# Adafruit_Feather_RP2040_Prop-Maker.net
KiCad netlist of a schematic drawn in EAGLE
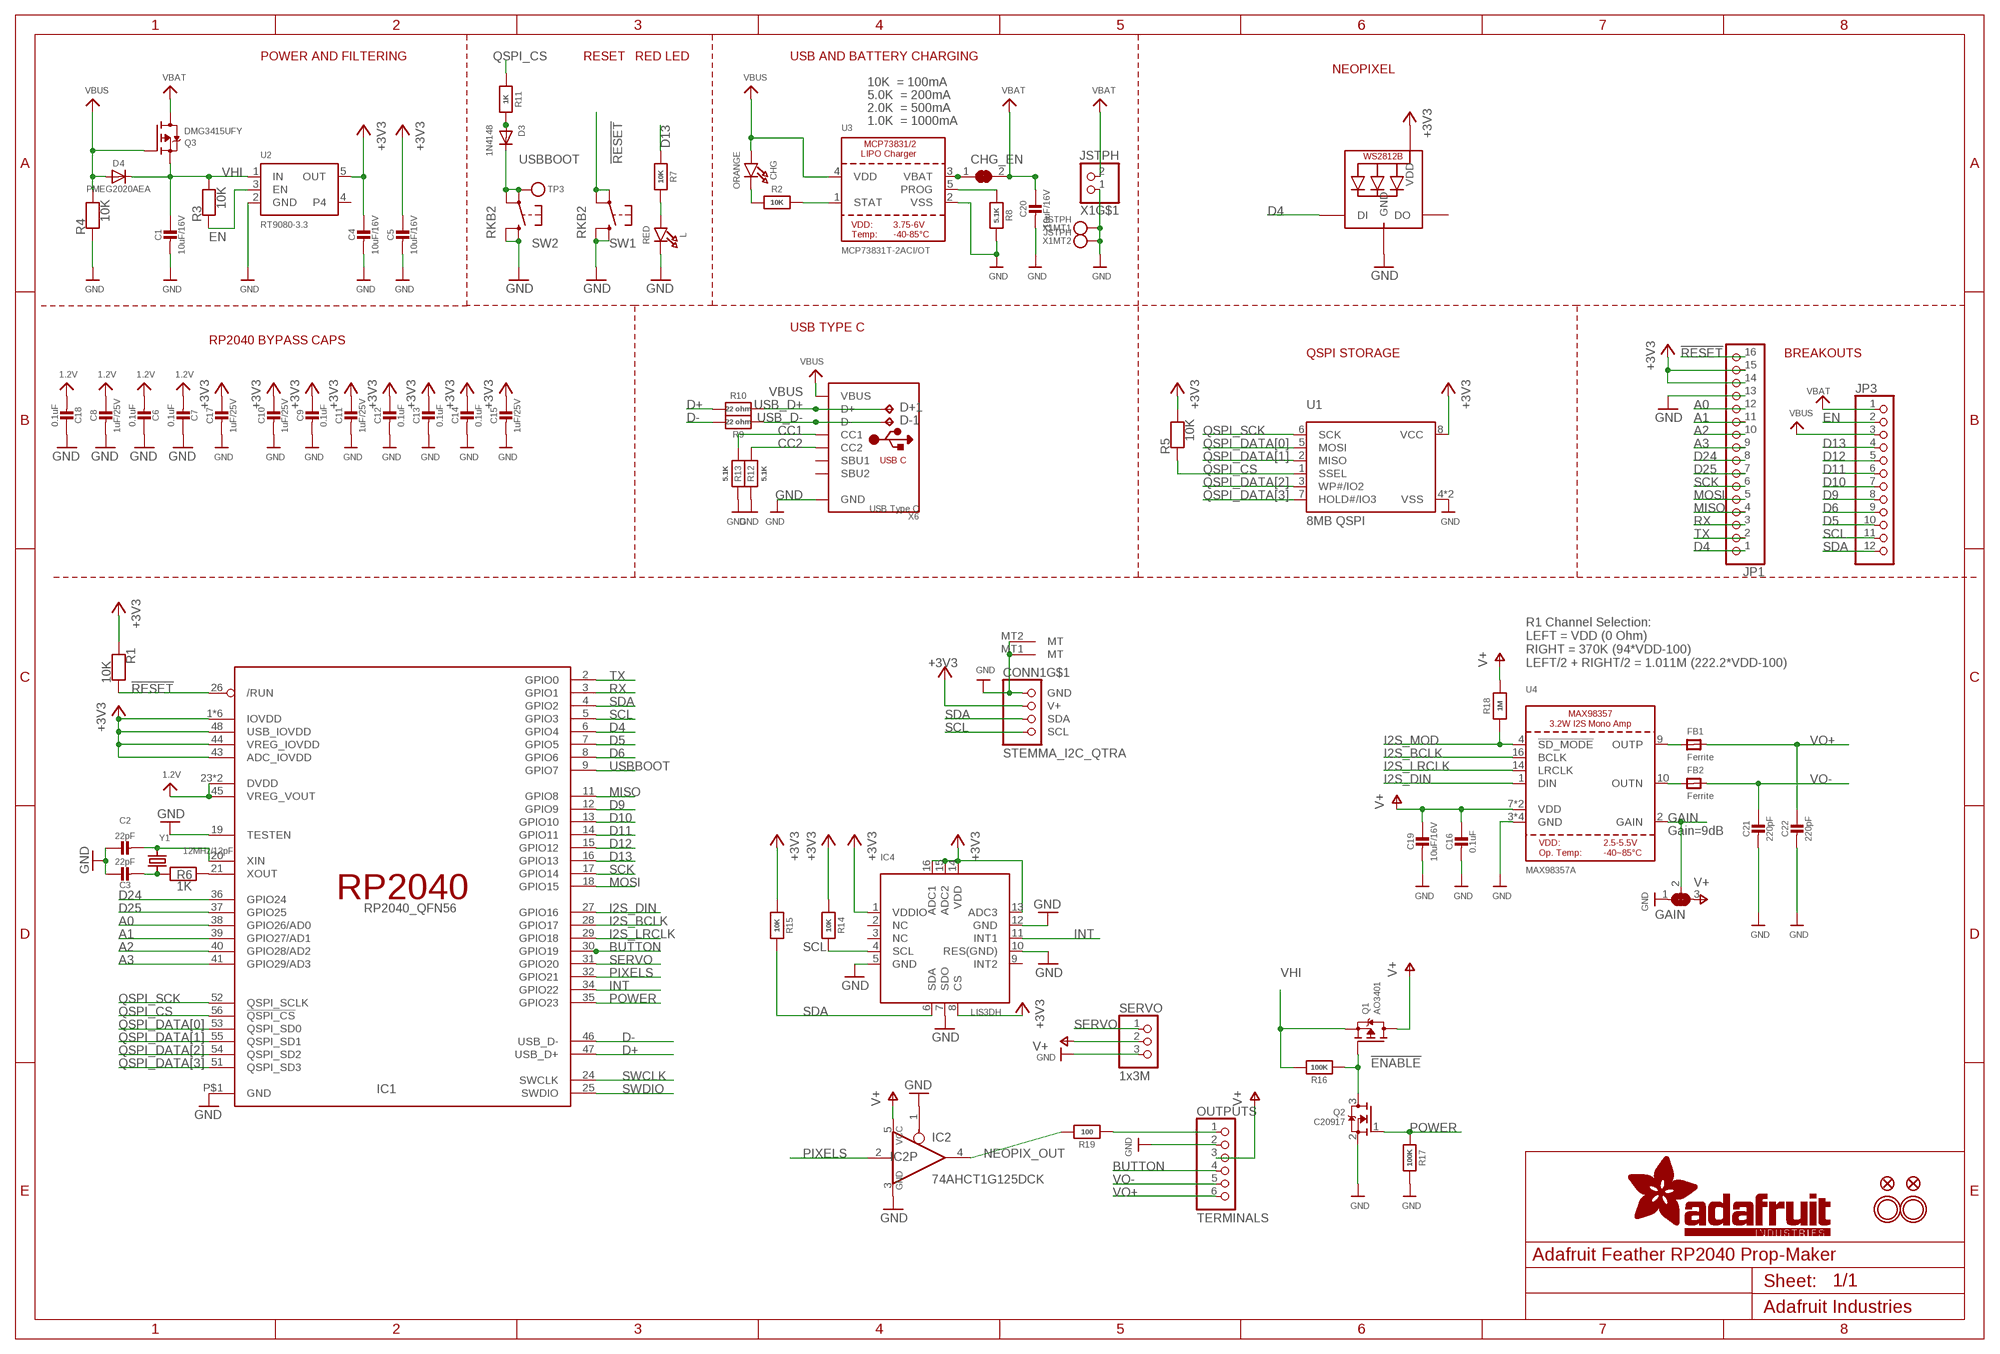
[diagram p0: schematic, sheet 1]

(export (version "E")
  (design (tool "Eeschema 10.0.6"))
  (components
    (comp (ref "C1")
      (value "10uF/16V")
      (footprint "eagle-import:0805-NO")
      (libsource (lib "eagle-import") (part "CAP_CERAMIC0805-NOOUTLINE"))
    )
    (comp (ref "C2")
      (value "22pF")
      (footprint "eagle-import:_0402NO")
      (libsource (lib "eagle-import") (part "CAP_CERAMIC_0402NO"))
    )
    (comp (ref "C3")
      (value "22pF")
      (footprint "eagle-import:_0402NO")
      (libsource (lib "eagle-import") (part "CAP_CERAMIC_0402NO"))
    )
    (comp (ref "C4")
      (value "10uF/16V")
      (footprint "eagle-import:0805-NO")
      (fields (field (name "REV") "B"))
      (libsource (lib "eagle-import") (part "CAP_CERAMIC0805-NOOUTLINE"))
    )
    (comp (ref "C5")
      (value "10uF/16V")
      (footprint "eagle-import:0805-NO")
      (libsource (lib "eagle-import") (part "CAP_CERAMIC0805-NOOUTLINE"))
    )
    (comp (ref "C6")
      (value "0.1uF")
      (footprint "eagle-import:_0402NO")
      (libsource (lib "eagle-import") (part "CAP_CERAMIC_0402NO"))
    )
    (comp (ref "C7")
      (value "0.1uF")
      (footprint "eagle-import:_0402NO")
      (libsource (lib "eagle-import") (part "CAP_CERAMIC_0402NO"))
    )
    (comp (ref "C8")
      (value "1uF/25V")
      (footprint "eagle-import:_0402NO")
      (libsource (lib "eagle-import") (part "CAP_CERAMIC_0402NO"))
    )
    (comp (ref "C9")
      (value "0.1uF")
      (footprint "eagle-import:_0402NO")
      (libsource (lib "eagle-import") (part "CAP_CERAMIC_0402NO"))
    )
    (comp (ref "C10")
      (value "1uF/25V")
      (footprint "eagle-import:_0402NO")
      (libsource (lib "eagle-import") (part "CAP_CERAMIC_0402NO"))
    )
    (comp (ref "C11")
      (value "1uF/25V")
      (footprint "eagle-import:_0402NO")
      (libsource (lib "eagle-import") (part "CAP_CERAMIC_0402NO"))
    )
    (comp (ref "C12")
      (value "0.1uF")
      (footprint "eagle-import:_0402NO")
      (libsource (lib "eagle-import") (part "CAP_CERAMIC_0402NO"))
    )
    (comp (ref "C13")
      (value "0.1uF")
      (footprint "eagle-import:_0402NO")
      (libsource (lib "eagle-import") (part "CAP_CERAMIC_0402NO"))
    )
    (comp (ref "C14")
      (value "0.1uF")
      (footprint "eagle-import:_0402NO")
      (libsource (lib "eagle-import") (part "CAP_CERAMIC_0402NO"))
    )
    (comp (ref "C15")
      (value "1uF/25V")
      (footprint "eagle-import:_0402NO")
      (libsource (lib "eagle-import") (part "CAP_CERAMIC_0402NO"))
    )
    (comp (ref "C16")
      (value "0.1uF")
      (footprint "eagle-import:_0402NO")
      (libsource (lib "eagle-import") (part "CAP_CERAMIC_0402NO"))
    )
    (comp (ref "C17")
      (value "1uF/25V")
      (footprint "eagle-import:_0402NO")
      (libsource (lib "eagle-import") (part "CAP_CERAMIC_0402NO"))
    )
    (comp (ref "C18")
      (value "0.1uF")
      (footprint "eagle-import:_0402NO")
      (libsource (lib "eagle-import") (part "CAP_CERAMIC_0402NO"))
    )
    (comp (ref "C19")
      (value "10uF/16V")
      (footprint "eagle-import:0805-NO")
      (libsource (lib "eagle-import") (part "CAP_CERAMIC0805-NOOUTLINE"))
    )
    (comp (ref "C20")
      (value "10uF/16V")
      (footprint "eagle-import:0805-NO")
      (libsource (lib "eagle-import") (part "CAP_CERAMIC0805-NOOUTLINE"))
    )
    (comp (ref "C21")
      (value "220pF")
      (footprint "eagle-import:_0402NO")
      (libsource (lib "eagle-import") (part "CAP_CERAMIC_0402NO"))
    )
    (comp (ref "C22")
      (value "220pF")
      (footprint "eagle-import:_0402NO")
      (libsource (lib "eagle-import") (part "CAP_CERAMIC_0402NO"))
    )
    (comp (ref "CHG")
      (value "ORANGE")
      (footprint "eagle-import:CHIPLED_0603_NOOUTLINE")
      (libsource (lib "eagle-import") (part "LED0603_NOOUTLINE"))
    )
    (comp (ref "CHG_EN")
      (value "SOLDERJUMPER_CLOSED")
      (footprint "eagle-import:SOLDERJUMPER_CLOSEDWIRE")
      (libsource (lib "eagle-import") (part "SOLDERJUMPER_CLOSED"))
    )
    (comp (ref "CONN1")
      (value "STEMMA_I2C_QTRA")
      (footprint "eagle-import:JST_SH4_RA")
      (libsource (lib "eagle-import") (part "STEMMA_I2C_QTRA"))
    )
    (comp (ref "D+1")
      (value "TPB1,27")
      (footprint "eagle-import:B1,27")
      (libsource (lib "eagle-import") (part "TPB1,27"))
    )
    (comp (ref "D-1")
      (value "TPB1,27")
      (footprint "eagle-import:B1,27")
      (libsource (lib "eagle-import") (part "TPB1,27"))
    )
    (comp (ref "D3")
      (value "1N4148")
      (footprint "eagle-import:SOD-323_MINI")
      (libsource (lib "eagle-import") (part "DIODE_SOD323MINI"))
    )
    (comp (ref "D4")
      (value "PMEG2020AEA")
      (footprint "eagle-import:SOD-323F")
      (libsource (lib "eagle-import") (part "DIODESOD-323F"))
    )
    (comp (ref "FB1")
      (value "Ferrite")
      (footprint "eagle-import:0603-NO")
      (libsource (lib "eagle-import") (part "FERRITE-0603NO"))
    )
    (comp (ref "FB2")
      (value "Ferrite")
      (footprint "eagle-import:0603-NO")
      (libsource (lib "eagle-import") (part "FERRITE-0603NO"))
    )
    (comp (ref "GAIN")
      (value "SOLDERJUMPER_2WAY")
      (footprint "eagle-import:SOLDERJUMPER_2WAY_OPEN_NOPASTE")
      (libsource (lib "eagle-import") (part "SOLDERJUMPER_2WAY"))
    )
    (comp (ref "IC1")
      (value "RP2040_QFN56")
      (footprint "eagle-import:QFN56_7MM_REDUCEDEPAD")
      (libsource (lib "eagle-import") (part "RP2040_QFN56"))
    )
    (comp (ref "IC2")
      (value "74AHCT1G125DCK")
      (footprint "eagle-import:SC70-5")
      (libsource (lib "eagle-import") (part "741G125DCKAHCT"))
    )
    (comp (ref "IC4")
      (value "LIS3DH")
      (footprint "eagle-import:LGA16_3X3MM")
      (libsource (lib "eagle-import") (part "ACCEL_LIS3DHTR"))
    )
    (comp (ref "JP1")
      (value "HEADER-1X16ROUND")
      (footprint "eagle-import:1X16_ROUND")
      (libsource (lib "eagle-import") (part "HEADER-1X16ROUND"))
    )
    (comp (ref "JP3")
      (value "HEADER-1X12")
      (footprint "eagle-import:1X12_ROUND")
      (libsource (lib "eagle-import") (part "HEADER-1X12"))
    )
    (comp (ref "L")
      (value "RED")
      (footprint "eagle-import:CHIPLED_0603_NOOUTLINE")
      (libsource (lib "eagle-import") (part "LED0603_NOOUTLINE"))
    )
    (comp (ref "LED1")
      (value "WS2812B_SK6805_1515")
      (footprint "eagle-import:SK6805_1515")
      (libsource (lib "eagle-import") (part "WS2812B_SK6805_1515"))
    )
    (comp (ref "OUTPUTS")
      (value "TERMINALS")
      (footprint "eagle-import:1X06_OVAL")
      (libsource (lib "eagle-import") (part "HEADER-1X6"))
    )
    (comp (ref "Q1")
      (value "AO3401")
      (footprint "eagle-import:SOT23-WIDE")
      (libsource (lib "eagle-import") (part "MOSFET-PWIDE"))
    )
    (comp (ref "Q2")
      (value "C20917")
      (footprint "eagle-import:SOT23-WIDE")
      (libsource (lib "eagle-import") (part "MOSFET-NWIDE"))
    )
    (comp (ref "Q3")
      (value "DMG3415UFY")
      (footprint "eagle-import:DFN2015-3")
      (libsource (lib "eagle-import") (part "MOSFET-P_DFN2015"))
    )
    (comp (ref "R1")
      (value "10K")
      (footprint "eagle-import:_0402NO")
      (libsource (lib "eagle-import") (part "RESISTOR_0402NO"))
    )
    (comp (ref "R2")
      (value "10K")
      (footprint "eagle-import:_0402NO")
      (libsource (lib "eagle-import") (part "RESISTOR_0402NO"))
    )
    (comp (ref "R3")
      (value "10K")
      (footprint "eagle-import:_0402NO")
      (libsource (lib "eagle-import") (part "RESISTOR_0402NO"))
    )
    (comp (ref "R4")
      (value "10K")
      (footprint "eagle-import:_0402NO")
      (libsource (lib "eagle-import") (part "RESISTOR_0402NO"))
    )
    (comp (ref "R5")
      (value "10K")
      (footprint "eagle-import:_0402NO")
      (libsource (lib "eagle-import") (part "RESISTOR_0402NO"))
    )
    (comp (ref "R6")
      (value "1K")
      (footprint "eagle-import:_0402NO")
      (libsource (lib "eagle-import") (part "RESISTOR_0402NO"))
    )
    (comp (ref "R7")
      (value "10K")
      (footprint "eagle-import:_0402NO")
      (libsource (lib "eagle-import") (part "RESISTOR_0402NO"))
    )
    (comp (ref "R8")
      (value "5.1K")
      (footprint "eagle-import:_0402NO")
      (libsource (lib "eagle-import") (part "RESISTOR_0402NO"))
    )
    (comp (ref "R9")
      (value "22 ohm")
      (footprint "eagle-import:_0402NO")
      (libsource (lib "eagle-import") (part "RESISTOR_0402NO"))
    )
    (comp (ref "R10")
      (value "22 ohm")
      (footprint "eagle-import:_0402NO")
      (libsource (lib "eagle-import") (part "RESISTOR_0402NO"))
    )
    (comp (ref "R11")
      (value "1K")
      (footprint "eagle-import:_0402NO")
      (libsource (lib "eagle-import") (part "RESISTOR_0402NO"))
    )
    (comp (ref "R12")
      (value "5.1K")
      (footprint "eagle-import:_0402NO")
      (libsource (lib "eagle-import") (part "RESISTOR_0402NO"))
    )
    (comp (ref "R13")
      (value "5.1K")
      (footprint "eagle-import:_0402NO")
      (libsource (lib "eagle-import") (part "RESISTOR_0402NO"))
    )
    (comp (ref "R14")
      (value "10K")
      (footprint "eagle-import:_0402NO")
      (libsource (lib "eagle-import") (part "RESISTOR_0402NO"))
    )
    (comp (ref "R15")
      (value "10K")
      (footprint "eagle-import:_0402NO")
      (libsource (lib "eagle-import") (part "RESISTOR_0402NO"))
    )
    (comp (ref "R16")
      (value "100K")
      (footprint "eagle-import:_0402NO")
      (libsource (lib "eagle-import") (part "RESISTOR_0402NO"))
    )
    (comp (ref "R17")
      (value "100K")
      (footprint "eagle-import:_0402NO")
      (libsource (lib "eagle-import") (part "RESISTOR_0402NO"))
    )
    (comp (ref "R18")
      (value "1M")
      (footprint "eagle-import:_0402NO")
      (libsource (lib "eagle-import") (part "RESISTOR_0402NO"))
    )
    (comp (ref "R19")
      (value "100")
      (footprint "eagle-import:_0402NO")
      (libsource (lib "eagle-import") (part "RESISTOR_0402NO"))
    )
    (comp (ref "SERVO")
      (value "1x3M")
      (footprint "eagle-import:1X03_ROUND_76")
      (libsource (lib "eagle-import") (part "HEADER-1X376MIL"))
    )
    (comp (ref "SW1")
      (value "RKB2")
      (footprint "eagle-import:BTN_RKB2_4.6X2.8")
      (libsource (lib "eagle-import") (part "SWITCH_TACT_SMT_RKB2"))
    )
    (comp (ref "SW2")
      (value "RKB2")
      (footprint "eagle-import:BTN_RKB2_4.6X2.8")
      (libsource (lib "eagle-import") (part "SWITCH_TACT_SMT_RKB2"))
    )
    (comp (ref "TP3")
      (value "TESTPOINTROUND1.5MMNO")
      (footprint "eagle-import:TESTPOINT_ROUND_1.5MM_NO")
      (libsource (lib "eagle-import") (part "TESTPOINTROUND1.5MMNO"))
    )
    (comp (ref "U$31")
      (value "MOUNTINGHOLE2.5")
      (footprint "eagle-import:MOUNTINGHOLE_2.5_PLATED")
      (libsource (lib "eagle-import") (part "MOUNTINGHOLE2.5"))
    )
    (comp (ref "U$32")
      (value "MOUNTINGHOLE2.5")
      (footprint "eagle-import:MOUNTINGHOLE_2.5_PLATED")
      (libsource (lib "eagle-import") (part "MOUNTINGHOLE2.5"))
    )
    (comp (ref "U$34")
      (value "FIDUCIAL_1MM")
      (footprint "eagle-import:FIDUCIAL_1MM")
      (libsource (lib "eagle-import") (part "FIDUCIAL_1MM"))
    )
    (comp (ref "U$35")
      (value "FIDUCIAL_1MM")
      (footprint "eagle-import:FIDUCIAL_1MM")
      (libsource (lib "eagle-import") (part "FIDUCIAL_1MM"))
    )
    (comp (ref "U1")
      (value "8MB QSPI")
      (footprint "eagle-import:USON8_4X4")
      (libsource (lib "eagle-import") (part "SPIFLASH_8PIN_4X4"))
    )
    (comp (ref "U2")
      (value "RT9080-3.3")
      (footprint "eagle-import:SOT23-5")
      (fields (field (name "JLC_ROTATION") "0"))
      (libsource (lib "eagle-import") (part "VREG_SOT23-5"))
    )
    (comp (ref "U3")
      (value "MCP73831T-2ACI/OT")
      (footprint "eagle-import:SOT23-5")
      (fields (field (name "JLC_ROTATION") "0"))
      (libsource (lib "eagle-import") (part "MCP73831/2"))
    )
    (comp (ref "U4")
      (value "MAX98357A")
      (footprint "eagle-import:QFN16_3MM")
      (libsource (lib "eagle-import") (part "AUDIOAMP_MAX98357"))
    )
    (comp (ref "X1")
      (value "JSTPH")
      (footprint "eagle-import:JSTPH2_BATT")
      (libsource (lib "eagle-import") (part "CON_JST_PH_2PIN_MT_BATT"))
    )
    (comp (ref "X6")
      (value "USB Type C")
      (footprint "eagle-import:USB_C_CUSB31-CFM2AX-01-X")
      (libsource (lib "eagle-import") (part "USB_C"))
    )
    (comp (ref "Y1")
      (value "12MHz/12pF")
      (footprint "eagle-import:CRYSTAL_2.5X2")
      (libsource (lib "eagle-import") (part "CRYSTAL2.5X2.0"))
    )
  )
  (nets
    (net (code "1") (name "+3V3") (class "Default")
      (node (ref "C10") (pin "1") (pinfunction "1_1") (pintype "passive"))
      (node (ref "C11") (pin "1") (pinfunction "1_1") (pintype "passive"))
      (node (ref "C12") (pin "1") (pinfunction "1_1") (pintype "passive"))
      (node (ref "C13") (pin "1") (pinfunction "1_1") (pintype "passive"))
      (node (ref "C14") (pin "1") (pinfunction "1_1") (pintype "passive"))
      (node (ref "C15") (pin "1") (pinfunction "1_1") (pintype "passive"))
      (node (ref "C17") (pin "1") (pinfunction "1_1") (pintype "passive"))
      (node (ref "C4") (pin "1") (pinfunction "1_1") (pintype "passive"))
      (node (ref "C5") (pin "1") (pinfunction "1_1") (pintype "passive"))
      (node (ref "C9") (pin "1") (pinfunction "1_1") (pintype "passive"))
      (node (ref "CONN1") (pin "2") (pinfunction "V+_2") (pintype "passive"))
      (node (ref "IC1") (pin "1") (pinfunction "IOVDD_1") (pintype "power_in"))
      (node (ref "IC1") (pin "10") (pinfunction "IOVDD_10") (pintype "power_in"))
      (node (ref "IC1") (pin "22") (pinfunction "IOVDD_22") (pintype "power_in"))
      (node (ref "IC1") (pin "33") (pinfunction "IOVDD_33") (pintype "power_in"))
      (node (ref "IC1") (pin "42") (pinfunction "IOVDD_42") (pintype "power_in"))
      (node (ref "IC1") (pin "43") (pinfunction "ADC_IOVDD_43") (pintype "power_in"))
      (node (ref "IC1") (pin "44") (pinfunction "VREG_IOVDD_44") (pintype "power_in"))
      (node (ref "IC1") (pin "48") (pinfunction "USB_IOVDD_48") (pintype "power_in"))
      (node (ref "IC1") (pin "49") (pinfunction "IOVDD_49") (pintype "power_in"))
      (node (ref "IC4") (pin "1") (pinfunction "VDDIO_1") (pintype "power_in"))
      (node (ref "IC4") (pin "13") (pinfunction "ADC3_13") (pintype "input"))
      (node (ref "IC4") (pin "14") (pinfunction "VDD_14") (pintype "power_in"))
      (node (ref "IC4") (pin "15") (pinfunction "ADC2_15") (pintype "input"))
      (node (ref "IC4") (pin "16") (pinfunction "ADC1_16") (pintype "input"))
      (node (ref "IC4") (pin "8") (pinfunction "CS_8") (pintype "input"))
      (node (ref "JP1") (pin "14") (pinfunction "14_14") (pintype "passive"))
      (node (ref "JP1") (pin "15") (pinfunction "15_15") (pintype "passive"))
      (node (ref "LED1") (pin "2") (pinfunction "VDD_2") (pintype "power_in"))
      (node (ref "R1") (pin "1") (pinfunction "1_1") (pintype "passive"))
      (node (ref "R14") (pin "1") (pinfunction "1_1") (pintype "passive"))
      (node (ref "R15") (pin "1") (pinfunction "1_1") (pintype "passive"))
      (node (ref "R5") (pin "2") (pinfunction "2_2") (pintype "passive"))
      (node (ref "U1") (pin "8") (pinfunction "VCC_8") (pintype "bidirectional"))
      (node (ref "U2") (pin "5") (pinfunction "OUT_5") (pintype "power_in"))
    )
    (net (code "2") (name "/A0") (class "Default")
      (node (ref "IC1") (pin "38") (pinfunction "GPIO26/AD0_38") (pintype "bidirectional"))
      (node (ref "JP1") (pin "12") (pinfunction "12_12") (pintype "passive"))
    )
    (net (code "3") (name "/A1") (class "Default")
      (node (ref "IC1") (pin "39") (pinfunction "GPIO27/AD1_39") (pintype "bidirectional"))
      (node (ref "JP1") (pin "11") (pinfunction "11_11") (pintype "passive"))
    )
    (net (code "4") (name "/A2") (class "Default")
      (node (ref "IC1") (pin "40") (pinfunction "GPIO28/AD2_40") (pintype "bidirectional"))
      (node (ref "JP1") (pin "10") (pinfunction "10_10") (pintype "passive"))
    )
    (net (code "5") (name "/A3") (class "Default")
      (node (ref "IC1") (pin "41") (pinfunction "GPIO29/AD3_41") (pintype "bidirectional"))
      (node (ref "JP1") (pin "9") (pinfunction "9_9") (pintype "passive"))
    )
    (net (code "6") (name "/BUTTON") (class "Default")
      (node (ref "IC1") (pin "30") (pinfunction "GPIO19_30") (pintype "bidirectional"))
      (node (ref "OUTPUTS") (pin "4") (pinfunction "4_4") (pintype "passive"))
    )
    (net (code "7") (name "/CC1") (class "Default")
      (node (ref "R13") (pin "2") (pinfunction "2_2") (pintype "passive"))
      (node (ref "X6") (pin "A5") (pinfunction "CC1_A5") (pintype "bidirectional"))
    )
    (net (code "8") (name "/CC2") (class "Default")
      (node (ref "R12") (pin "2") (pinfunction "2_2") (pintype "passive"))
      (node (ref "X6") (pin "B5") (pinfunction "CC2_B5") (pintype "bidirectional"))
    )
    (net (code "9") (name "/D+") (class "Default")
      (node (ref "IC1") (pin "47") (pinfunction "USB_D+_47") (pintype "bidirectional"))
      (node (ref "R10") (pin "2") (pinfunction "2_2") (pintype "passive"))
    )
    (net (code "10") (name "/D-") (class "Default")
      (node (ref "IC1") (pin "46") (pinfunction "USB_D-_46") (pintype "bidirectional"))
      (node (ref "R9") (pin "2") (pinfunction "2_2") (pintype "passive"))
    )
    (net (code "11") (name "/D4") (class "Default")
      (node (ref "IC1") (pin "6") (pinfunction "GPIO4_6") (pintype "bidirectional"))
      (node (ref "JP1") (pin "1") (pinfunction "1_1") (pintype "passive"))
      (node (ref "LED1") (pin "1") (pinfunction "DI_1") (pintype "input"))
    )
    (net (code "12") (name "/D5") (class "Default")
      (node (ref "IC1") (pin "7") (pinfunction "GPIO5_7") (pintype "bidirectional"))
      (node (ref "JP3") (pin "10") (pinfunction "10_10") (pintype "passive"))
    )
    (net (code "13") (name "/D6") (class "Default")
      (node (ref "IC1") (pin "8") (pinfunction "GPIO6_8") (pintype "bidirectional"))
      (node (ref "JP3") (pin "9") (pinfunction "9_9") (pintype "passive"))
    )
    (net (code "14") (name "/D9") (class "Default")
      (node (ref "IC1") (pin "12") (pinfunction "GPIO9_12") (pintype "bidirectional"))
      (node (ref "JP3") (pin "8") (pinfunction "8_8") (pintype "passive"))
    )
    (net (code "15") (name "/D10") (class "Default")
      (node (ref "IC1") (pin "13") (pinfunction "GPIO10_13") (pintype "bidirectional"))
      (node (ref "JP3") (pin "7") (pinfunction "7_7") (pintype "passive"))
    )
    (net (code "16") (name "/D11") (class "Default")
      (node (ref "IC1") (pin "14") (pinfunction "GPIO11_14") (pintype "bidirectional"))
      (node (ref "JP3") (pin "6") (pinfunction "6_6") (pintype "passive"))
    )
    (net (code "17") (name "/D12") (class "Default")
      (node (ref "IC1") (pin "15") (pinfunction "GPIO12_15") (pintype "bidirectional"))
      (node (ref "JP3") (pin "5") (pinfunction "5_5") (pintype "passive"))
    )
    (net (code "18") (name "/D13") (class "Default")
      (node (ref "IC1") (pin "16") (pinfunction "GPIO13_16") (pintype "bidirectional"))
      (node (ref "JP3") (pin "4") (pinfunction "4_4") (pintype "passive"))
      (node (ref "R7") (pin "1") (pinfunction "1_1") (pintype "passive"))
    )
    (net (code "19") (name "/D24") (class "Default")
      (node (ref "IC1") (pin "36") (pinfunction "GPIO24_36") (pintype "bidirectional"))
      (node (ref "JP1") (pin "8") (pinfunction "8_8") (pintype "passive"))
    )
    (net (code "20") (name "/D25") (class "Default")
      (node (ref "IC1") (pin "37") (pinfunction "GPIO25_37") (pintype "bidirectional"))
      (node (ref "JP1") (pin "7") (pinfunction "7_7") (pintype "passive"))
    )
    (net (code "21") (name "/EN") (class "Default")
      (node (ref "JP3") (pin "2") (pinfunction "2_2") (pintype "passive"))
      (node (ref "R3") (pin "1") (pinfunction "1_1") (pintype "passive"))
      (node (ref "U2") (pin "3") (pinfunction "EN_3") (pintype "input"))
    )
    (net (code "22") (name "/GAIN") (class "Default")
      (node (ref "GAIN") (pin "2") (pinfunction "2_2") (pintype "passive"))
      (node (ref "U4") (pin "2") (pinfunction "GAIN_2") (pintype "bidirectional"))
    )
    (net (code "23") (name "/I2S_BCLK") (class "Default")
      (node (ref "IC1") (pin "28") (pinfunction "GPIO17_28") (pintype "bidirectional"))
      (node (ref "U4") (pin "16") (pinfunction "BCLK_16") (pintype "bidirectional"))
    )
    (net (code "24") (name "/I2S_DIN") (class "Default")
      (node (ref "IC1") (pin "27") (pinfunction "GPIO16_27") (pintype "bidirectional"))
      (node (ref "U4") (pin "1") (pinfunction "DIN_1") (pintype "bidirectional"))
    )
    (net (code "25") (name "/I2S_LRCLK") (class "Default")
      (node (ref "IC1") (pin "29") (pinfunction "GPIO18_29") (pintype "bidirectional"))
      (node (ref "U4") (pin "14") (pinfunction "LRCLK_14") (pintype "bidirectional"))
    )
    (net (code "26") (name "/I2S_MOD") (class "Default")
      (node (ref "R18") (pin "1") (pinfunction "1_1") (pintype "passive"))
      (node (ref "U4") (pin "4") (pinfunction "~{SD_MODE}_4") (pintype "bidirectional"))
    )
    (net (code "27") (name "/INT") (class "Default")
      (node (ref "IC1") (pin "34") (pinfunction "GPIO22_34") (pintype "bidirectional"))
      (node (ref "IC4") (pin "11") (pinfunction "INT1_11") (pintype "output"))
    )
    (net (code "28") (name "/MISO") (class "Default")
      (node (ref "IC1") (pin "11") (pinfunction "GPIO8_11") (pintype "bidirectional"))
      (node (ref "JP1") (pin "4") (pinfunction "4_4") (pintype "passive"))
    )
    (net (code "29") (name "/MOSI") (class "Default")
      (node (ref "IC1") (pin "18") (pinfunction "GPIO15_18") (pintype "bidirectional"))
      (node (ref "JP1") (pin "5") (pinfunction "5_5") (pintype "passive"))
    )
    (net (code "30") (name "/NEOPIX_OUT") (class "Default")
      (node (ref "IC2") (pin "4") (pinfunction "O_4") (pintype "tri_state"))
      (node (ref "R19") (pin "2") (pinfunction "2_2") (pintype "passive"))
    )
    (net (code "31") (name "/PIXELS") (class "Default")
      (node (ref "IC1") (pin "32") (pinfunction "GPIO21_32") (pintype "bidirectional"))
      (node (ref "IC2") (pin "2") (pinfunction "I_2") (pintype "input"))
    )
    (net (code "32") (name "/POWER") (class "Default")
      (node (ref "IC1") (pin "35") (pinfunction "GPIO23_35") (pintype "bidirectional"))
      (node (ref "Q2") (pin "1") (pinfunction "G_1") (pintype "bidirectional"))
      (node (ref "R17") (pin "1") (pinfunction "1_1") (pintype "passive"))
    )
    (net (code "33") (name "/QSPI_CS") (class "Default")
      (node (ref "IC1") (pin "56") (pinfunction "~{QSPI_CS}_56") (pintype "bidirectional"))
      (node (ref "R11") (pin "1") (pinfunction "1_1") (pintype "passive"))
      (node (ref "R5") (pin "1") (pinfunction "1_1") (pintype "passive"))
      (node (ref "U1") (pin "1") (pinfunction "SSEL_1") (pintype "bidirectional"))
    )
    (net (code "34") (name "/QSPI_DATA[0]") (class "Default")
      (node (ref "IC1") (pin "53") (pinfunction "QSPI_SD0_53") (pintype "bidirectional"))
      (node (ref "U1") (pin "5") (pinfunction "MOSI_5") (pintype "bidirectional"))
    )
    (net (code "35") (name "/QSPI_DATA[1]") (class "Default")
      (node (ref "IC1") (pin "55") (pinfunction "QSPI_SD1_55") (pintype "bidirectional"))
      (node (ref "U1") (pin "2") (pinfunction "MISO_2") (pintype "bidirectional"))
    )
    (net (code "36") (name "/QSPI_DATA[2]") (class "Default")
      (node (ref "IC1") (pin "54") (pinfunction "QSPI_SD2_54") (pintype "bidirectional"))
      (node (ref "U1") (pin "3") (pinfunction "WP#/IO2_3") (pintype "bidirectional"))
    )
    (net (code "37") (name "/QSPI_DATA[3]") (class "Default")
      (node (ref "IC1") (pin "51") (pinfunction "QSPI_SD3_51") (pintype "bidirectional"))
      (node (ref "U1") (pin "7") (pinfunction "HOLD#/IO3_7") (pintype "bidirectional"))
    )
    (net (code "38") (name "/QSPI_SCK") (class "Default")
      (node (ref "IC1") (pin "52") (pinfunction "QSPI_SCLK_52") (pintype "bidirectional"))
      (node (ref "U1") (pin "6") (pinfunction "SCK_6") (pintype "bidirectional"))
    )
    (net (code "39") (name "/RX") (class "Default")
      (node (ref "IC1") (pin "3") (pinfunction "GPIO1_3") (pintype "bidirectional"))
      (node (ref "JP1") (pin "3") (pinfunction "3_3") (pintype "passive"))
    )
    (net (code "40") (name "/SCK") (class "Default")
      (node (ref "IC1") (pin "17") (pinfunction "GPIO14_17") (pintype "bidirectional"))
      (node (ref "JP1") (pin "6") (pinfunction "6_6") (pintype "passive"))
    )
    (net (code "41") (name "/SCL") (class "Default")
      (node (ref "CONN1") (pin "4") (pinfunction "SCL_4") (pintype "passive"))
      (node (ref "IC1") (pin "5") (pinfunction "GPIO3_5") (pintype "bidirectional"))
      (node (ref "IC4") (pin "4") (pinfunction "SCL_4") (pintype "bidirectional"))
      (node (ref "JP3") (pin "11") (pinfunction "11_11") (pintype "passive"))
      (node (ref "R14") (pin "2") (pinfunction "2_2") (pintype "passive"))
    )
    (net (code "42") (name "/SDA") (class "Default")
      (node (ref "CONN1") (pin "3") (pinfunction "SDA_3") (pintype "passive"))
      (node (ref "IC1") (pin "4") (pinfunction "GPIO2_4") (pintype "bidirectional"))
      (node (ref "IC4") (pin "6") (pinfunction "SDA_6") (pintype "bidirectional"))
      (node (ref "JP3") (pin "12") (pinfunction "12_12") (pintype "passive"))
      (node (ref "R15") (pin "2") (pinfunction "2_2") (pintype "passive"))
    )
    (net (code "43") (name "/SERVO") (class "Default")
      (node (ref "IC1") (pin "31") (pinfunction "GPIO20_31") (pintype "bidirectional"))
      (node (ref "SERVO") (pin "1") (pinfunction "1_1") (pintype "passive"))
    )
    (net (code "44") (name "/SWCLK") (class "Default")
      (node (ref "IC1") (pin "24") (pinfunction "SWCLK_24") (pintype "bidirectional"))
    )
    (net (code "45") (name "/SWDIO") (class "Default")
      (node (ref "IC1") (pin "25") (pinfunction "SWDIO_25") (pintype "bidirectional"))
    )
    (net (code "46") (name "/TX") (class "Default")
      (node (ref "IC1") (pin "2") (pinfunction "GPIO0_2") (pintype "bidirectional"))
      (node (ref "JP1") (pin "2") (pinfunction "2_2") (pintype "passive"))
    )
    (net (code "47") (name "/USBBOOT") (class "Default")
      (node (ref "D3") (pin "C") (pinfunction "C_C") (pintype "passive"))
      (node (ref "IC1") (pin "9") (pinfunction "GPIO7_9") (pintype "bidirectional"))
      (node (ref "SW2") (pin "A") (pinfunction "P_A") (pintype "passive"))
      (node (ref "SW2") (pin "A'") (pinfunction "P1_A'") (pintype "passive"))
      (node (ref "TP3") (pin "P$1") (pinfunction "P$1_P$1") (pintype "bidirectional"))
    )
    (net (code "48") (name "/USB_D+") (class "Default")
      (node (ref "D+1") (pin "TP") (pinfunction "TP_TP") (pintype "input"))
      (node (ref "R10") (pin "1") (pinfunction "1_1") (pintype "passive"))
      (node (ref "X6") (pin "A6") (pinfunction "D+_A6") (pintype "bidirectional"))
      (node (ref "X6") (pin "B6") (pinfunction "D+_B6") (pintype "bidirectional"))
    )
    (net (code "49") (name "/USB_D-") (class "Default")
      (node (ref "D-1") (pin "TP") (pinfunction "TP_TP") (pintype "input"))
      (node (ref "R9") (pin "1") (pinfunction "1_1") (pintype "passive"))
      (node (ref "X6") (pin "A7") (pinfunction "D-_A7") (pintype "bidirectional"))
      (node (ref "X6") (pin "B7") (pinfunction "D-_B7") (pintype "bidirectional"))
    )
    (net (code "50") (name "/VHI") (class "Default")
      (node (ref "C1") (pin "1") (pinfunction "1_1") (pintype "passive"))
      (node (ref "D4") (pin "C") (pinfunction "C_C") (pintype "passive"))
      (node (ref "Q1") (pin "2") (pinfunction "S_2") (pintype "passive"))
      (node (ref "Q3") (pin "2") (pinfunction "S_2") (pintype "passive"))
      (node (ref "R16") (pin "2") (pinfunction "2_2") (pintype "passive"))
      (node (ref "R3") (pin "2") (pinfunction "2_2") (pintype "passive"))
      (node (ref "U2") (pin "1") (pinfunction "IN_1") (pintype "power_in"))
    )
    (net (code "51") (name "/VO+") (class "Default")
      (node (ref "C22") (pin "1") (pinfunction "1_1") (pintype "passive"))
      (node (ref "FB1") (pin "2") (pinfunction "P$2_2") (pintype "passive"))
      (node (ref "OUTPUTS") (pin "6") (pinfunction "6_6") (pintype "passive"))
    )
    (net (code "52") (name "/VO-") (class "Default")
      (node (ref "C21") (pin "1") (pinfunction "1_1") (pintype "passive"))
      (node (ref "FB2") (pin "2") (pinfunction "P$2_2") (pintype "passive"))
      (node (ref "OUTPUTS") (pin "5") (pinfunction "5_5") (pintype "passive"))
    )
    (net (code "53") (name "/~{ENABLE}") (class "Default")
      (node (ref "Q1") (pin "1") (pinfunction "G_1") (pintype "passive"))
      (node (ref "Q2") (pin "3") (pinfunction "D_3") (pintype "bidirectional"))
      (node (ref "R16") (pin "1") (pinfunction "1_1") (pintype "passive"))
    )
    (net (code "54") (name "/~{RESET}") (class "Default")
      (node (ref "IC1") (pin "26") (pinfunction "/RUN_26") (pintype "bidirectional"))
      (node (ref "JP1") (pin "16") (pinfunction "16_16") (pintype "passive"))
      (node (ref "R1") (pin "2") (pinfunction "2_2") (pintype "passive"))
      (node (ref "SW1") (pin "A") (pinfunction "P_A") (pintype "passive"))
      (node (ref "SW1") (pin "A'") (pinfunction "P1_A'") (pintype "passive"))
    )
    (net (code "55") (name "1.2V") (class "Default")
      (node (ref "C18") (pin "2") (pinfunction "2_2") (pintype "passive"))
      (node (ref "C6") (pin "2") (pinfunction "2_2") (pintype "passive"))
      (node (ref "C7") (pin "2") (pinfunction "2_2") (pintype "passive"))
      (node (ref "C8") (pin "1") (pinfunction "1_1") (pintype "passive"))
      (node (ref "IC1") (pin "23") (pinfunction "DVDD_23") (pintype "power_in"))
      (node (ref "IC1") (pin "45") (pinfunction "VREG_VOUT_45") (pintype "power_in"))
      (node (ref "IC1") (pin "50") (pinfunction "DVDD_50") (pintype "power_in"))
    )
    (net (code "56") (name "GND") (class "Default")
      (node (ref "C1") (pin "2") (pinfunction "2_2") (pintype "passive"))
      (node (ref "C10") (pin "2") (pinfunction "2_2") (pintype "passive"))
      (node (ref "C11") (pin "2") (pinfunction "2_2") (pintype "passive"))
      (node (ref "C12") (pin "2") (pinfunction "2_2") (pintype "passive"))
      (node (ref "C13") (pin "2") (pinfunction "2_2") (pintype "passive"))
      (node (ref "C14") (pin "2") (pinfunction "2_2") (pintype "passive"))
      (node (ref "C15") (pin "2") (pinfunction "2_2") (pintype "passive"))
      (node (ref "C16") (pin "2") (pinfunction "2_2") (pintype "passive"))
      (node (ref "C17") (pin "2") (pinfunction "2_2") (pintype "passive"))
      (node (ref "C18") (pin "1") (pinfunction "1_1") (pintype "passive"))
      (node (ref "C19") (pin "2") (pinfunction "2_2") (pintype "passive"))
      (node (ref "C2") (pin "1") (pinfunction "1_1") (pintype "passive"))
      (node (ref "C20") (pin "2") (pinfunction "2_2") (pintype "passive"))
      (node (ref "C21") (pin "2") (pinfunction "2_2") (pintype "passive"))
      (node (ref "C22") (pin "2") (pinfunction "2_2") (pintype "passive"))
      (node (ref "C3") (pin "1") (pinfunction "1_1") (pintype "passive"))
      (node (ref "C4") (pin "2") (pinfunction "2_2") (pintype "passive"))
      (node (ref "C5") (pin "2") (pinfunction "2_2") (pintype "passive"))
      (node (ref "C6") (pin "1") (pinfunction "1_1") (pintype "passive"))
      (node (ref "C7") (pin "1") (pinfunction "1_1") (pintype "passive"))
      (node (ref "C8") (pin "2") (pinfunction "2_2") (pintype "passive"))
      (node (ref "C9") (pin "2") (pinfunction "2_2") (pintype "passive"))
      (node (ref "CONN1") (pin "1") (pinfunction "GND_1") (pintype "passive"))
      (node (ref "CONN1") (pin "MT1") (pinfunction "MT_MT1") (pintype "bidirectional"))
      (node (ref "CONN1") (pin "MT2") (pinfunction "MT_MT2") (pintype "bidirectional"))
      (node (ref "GAIN") (pin "1") (pinfunction "1_1") (pintype "passive"))
      (node (ref "IC1") (pin "19") (pinfunction "TESTEN_19") (pintype "input"))
      (node (ref "IC1") (pin "P$1") (pinfunction "GND_P$1") (pintype "power_in"))
      (node (ref "IC2") (pin "1") (pinfunction "OE_1") (pintype "input"))
      (node (ref "IC2") (pin "3") (pinfunction "GND_3") (pintype "power_in"))
      (node (ref "IC4") (pin "10") (pinfunction "RES(GND)_10") (pintype "bidirectional"))
      (node (ref "IC4") (pin "12") (pinfunction "GND_12") (pintype "power_in"))
      (node (ref "IC4") (pin "5") (pinfunction "GND_5") (pintype "power_in"))
      (node (ref "IC4") (pin "7") (pinfunction "SDO_7") (pintype "bidirectional"))
      (node (ref "JP1") (pin "13") (pinfunction "13_13") (pintype "passive"))
      (node (ref "L") (pin "C") (pinfunction "C_C") (pintype "passive"))
      (node (ref "LED1") (pin "4") (pinfunction "GND_4") (pintype "power_in"))
      (node (ref "OUTPUTS") (pin "2") (pinfunction "2_2") (pintype "passive"))
      (node (ref "Q2") (pin "2") (pinfunction "S_2") (pintype "bidirectional"))
      (node (ref "R12") (pin "1") (pinfunction "1_1") (pintype "passive"))
      (node (ref "R13") (pin "1") (pinfunction "1_1") (pintype "passive"))
      (node (ref "R17") (pin "2") (pinfunction "2_2") (pintype "passive"))
      (node (ref "R4") (pin "1") (pinfunction "1_1") (pintype "passive"))
      (node (ref "R8") (pin "2") (pinfunction "2_2") (pintype "passive"))
      (node (ref "SERVO") (pin "3") (pinfunction "3_3") (pintype "passive"))
      (node (ref "SW1") (pin "B") (pinfunction "S_B") (pintype "passive"))
      (node (ref "SW1") (pin "B'") (pinfunction "S1_B'") (pintype "passive"))
      (node (ref "SW2") (pin "B") (pinfunction "S_B") (pintype "passive"))
      (node (ref "SW2") (pin "B'") (pinfunction "S1_B'") (pintype "passive"))
      (node (ref "U1") (pin "4") (pinfunction "VSS_4") (pintype "bidirectional"))
      (node (ref "U1") (pin "PAD") (pinfunction "VSS_PAD") (pintype "bidirectional"))
      (node (ref "U2") (pin "2") (pinfunction "GND_2") (pintype "power_in"))
      (node (ref "U3") (pin "2") (pinfunction "VSS_2") (pintype "power_in"))
      (node (ref "U4") (pin "11") (pinfunction "GND_11") (pintype "power_in"))
      (node (ref "U4") (pin "15") (pinfunction "GND_15") (pintype "power_in"))
      (node (ref "U4") (pin "3") (pinfunction "GND_3") (pintype "power_in"))
      (node (ref "U4") (pin "THERMAL") (pinfunction "GND_THERMAL") (pintype "power_in"))
      (node (ref "X1") (pin "1") (pinfunction "1_1") (pintype "passive"))
      (node (ref "X1") (pin "NC1") (pinfunction "P$1_NC1") (pintype "bidirectional"))
      (node (ref "X1") (pin "NC2") (pinfunction "P$1_NC2") (pintype "bidirectional"))
      (node (ref "X6") (pin "A1B12") (pinfunction "GND_A1B12") (pintype "power_in"))
      (node (ref "X6") (pin "B1A12") (pinfunction "GND_B1A12") (pintype "power_in"))
    )
    (net (code "57") (name "Net-(C3-Pad2)") (class "Default")
      (node (ref "C3") (pin "2") (pinfunction "2_2") (pintype "passive"))
      (node (ref "R6") (pin "1") (pinfunction "1_1") (pintype "passive"))
      (node (ref "Y1") (pin "1") (pinfunction "1_1") (pintype "passive"))
    )
    (net (code "58") (name "Net-(CHG-PadC)") (class "Default")
      (node (ref "CHG") (pin "C") (pinfunction "C_C") (pintype "passive"))
      (node (ref "R2") (pin "1") (pinfunction "1_1") (pintype "passive"))
    )
    (net (code "59") (name "Net-(D3-PadA)") (class "Default")
      (node (ref "D3") (pin "A") (pinfunction "A_A") (pintype "passive"))
      (node (ref "R11") (pin "2") (pinfunction "2_2") (pintype "passive"))
    )
    (net (code "60") (name "Net-(FB1-P$1)") (class "Default")
      (node (ref "FB1") (pin "1") (pinfunction "P$1_1") (pintype "passive"))
      (node (ref "U4") (pin "9") (pinfunction "OUTP_9") (pintype "output"))
    )
    (net (code "61") (name "Net-(FB2-P$1)") (class "Default")
      (node (ref "FB2") (pin "1") (pinfunction "P$1_1") (pintype "passive"))
      (node (ref "U4") (pin "10") (pinfunction "OUTN_10") (pintype "output"))
    )
    (net (code "62") (name "Net-(IC1-XIN)") (class "Default")
      (node (ref "C2") (pin "2") (pinfunction "2_2") (pintype "passive"))
      (node (ref "IC1") (pin "20") (pinfunction "XIN_20") (pintype "input"))
      (node (ref "Y1") (pin "3") (pinfunction "2_3") (pintype "passive"))
    )
    (net (code "63") (name "Net-(IC1-XOUT)") (class "Default")
      (node (ref "IC1") (pin "21") (pinfunction "XOUT_21") (pintype "output"))
      (node (ref "R6") (pin "2") (pinfunction "2_2") (pintype "passive"))
    )
    (net (code "64") (name "Net-(L-PadA)") (class "Default")
      (node (ref "L") (pin "A") (pinfunction "A_A") (pintype "passive"))
      (node (ref "R7") (pin "2") (pinfunction "2_2") (pintype "passive"))
    )
    (net (code "65") (name "Net-(OUTPUTS-Pad1)") (class "Default")
      (node (ref "OUTPUTS") (pin "1") (pinfunction "1_1") (pintype "passive"))
      (node (ref "R19") (pin "1") (pinfunction "1_1") (pintype "passive"))
    )
    (net (code "66") (name "Net-(U3-PROG)") (class "Default")
      (node (ref "R8") (pin "1") (pinfunction "1_1") (pintype "passive"))
      (node (ref "U3") (pin "5") (pinfunction "PROG_5") (pintype "input"))
    )
    (net (code "67") (name "Net-(U3-STAT)") (class "Default")
      (node (ref "R2") (pin "2") (pinfunction "2_2") (pintype "passive"))
      (node (ref "U3") (pin "1") (pinfunction "STAT_1") (pintype "output"))
    )
    (net (code "68") (name "Net-(U3-VBAT)") (class "Default")
      (node (ref "CHG_EN") (pin "1") (pinfunction "1_1") (pintype "passive"))
      (node (ref "U3") (pin "3") (pinfunction "VBAT_3") (pintype "power_in"))
    )
    (net (code "69") (name "V+") (class "Default")
      (node (ref "C16") (pin "1") (pinfunction "1_1") (pintype "passive"))
      (node (ref "C19") (pin "1") (pinfunction "1_1") (pintype "passive"))
      (node (ref "GAIN") (pin "3") (pinfunction "3_3") (pintype "passive"))
      (node (ref "IC2") (pin "5") (pinfunction "VCC_5") (pintype "power_in"))
      (node (ref "OUTPUTS") (pin "3") (pinfunction "3_3") (pintype "passive"))
      (node (ref "Q1") (pin "3") (pinfunction "D_3") (pintype "passive"))
      (node (ref "R18") (pin "2") (pinfunction "2_2") (pintype "passive"))
      (node (ref "SERVO") (pin "2") (pinfunction "2_2") (pintype "passive"))
      (node (ref "U4") (pin "7") (pinfunction "VDD_7") (pintype "power_in"))
      (node (ref "U4") (pin "8") (pinfunction "VDD_8") (pintype "power_in"))
    )
    (net (code "70") (name "VBAT") (class "Default")
      (node (ref "C20") (pin "1") (pinfunction "1_1") (pintype "passive"))
      (node (ref "CHG_EN") (pin "2") (pinfunction "2_2") (pintype "passive"))
      (node (ref "JP3") (pin "1") (pinfunction "1_1") (pintype "passive"))
      (node (ref "Q3") (pin "3") (pinfunction "D_3") (pintype "passive"))
      (node (ref "X1") (pin "2") (pinfunction "2_2") (pintype "passive"))
    )
    (net (code "71") (name "VBUS") (class "Default")
      (node (ref "CHG") (pin "A") (pinfunction "A_A") (pintype "passive"))
      (node (ref "D4") (pin "A") (pinfunction "A_A") (pintype "passive"))
      (node (ref "JP3") (pin "3") (pinfunction "3_3") (pintype "passive"))
      (node (ref "Q3") (pin "1") (pinfunction "G_1") (pintype "passive"))
      (node (ref "R4") (pin "2") (pinfunction "2_2") (pintype "passive"))
      (node (ref "U3") (pin "4") (pinfunction "VDD_4") (pintype "power_in"))
      (node (ref "X6") (pin "A4B9") (pinfunction "VBUS_A4B9") (pintype "power_in"))
      (node (ref "X6") (pin "B4A9") (pinfunction "VBUS_B4A9") (pintype "power_in"))
    )
    (net (code "72") (name "unconnected-(IC4-INT2-Pad9)") (class "Default")
      (node (ref "IC4") (pin "9") (pinfunction "INT2_9") (pintype "output"))
    )
    (net (code "73") (name "unconnected-(IC4-NC-Pad2)") (class "Default")
      (node (ref "IC4") (pin "2") (pinfunction "NC_2") (pintype "no_connect"))
    )
    (net (code "74") (name "unconnected-(IC4-NC-Pad3)") (class "Default")
      (node (ref "IC4") (pin "3") (pinfunction "NC_3") (pintype "no_connect"))
    )
    (net (code "75") (name "unconnected-(LED1-DO-Pad3)") (class "Default")
      (node (ref "LED1") (pin "3") (pinfunction "DO_3") (pintype "output"))
    )
    (net (code "76") (name "unconnected-(U2-P4-Pad4)") (class "Default")
      (node (ref "U2") (pin "4") (pinfunction "P4_4") (pintype "bidirectional"))
    )
    (net (code "77") (name "unconnected-(X6-SBU1-PadA8)") (class "Default")
      (node (ref "X6") (pin "A8") (pinfunction "SBU1_A8") (pintype "bidirectional"))
    )
    (net (code "78") (name "unconnected-(X6-SBU2-PadB8)") (class "Default")
      (node (ref "X6") (pin "B8") (pinfunction "SBU2_B8") (pintype "bidirectional"))
    )
  )
)
